# mcu.net
KiCad netlist of a schematic drawn in Altium Designer
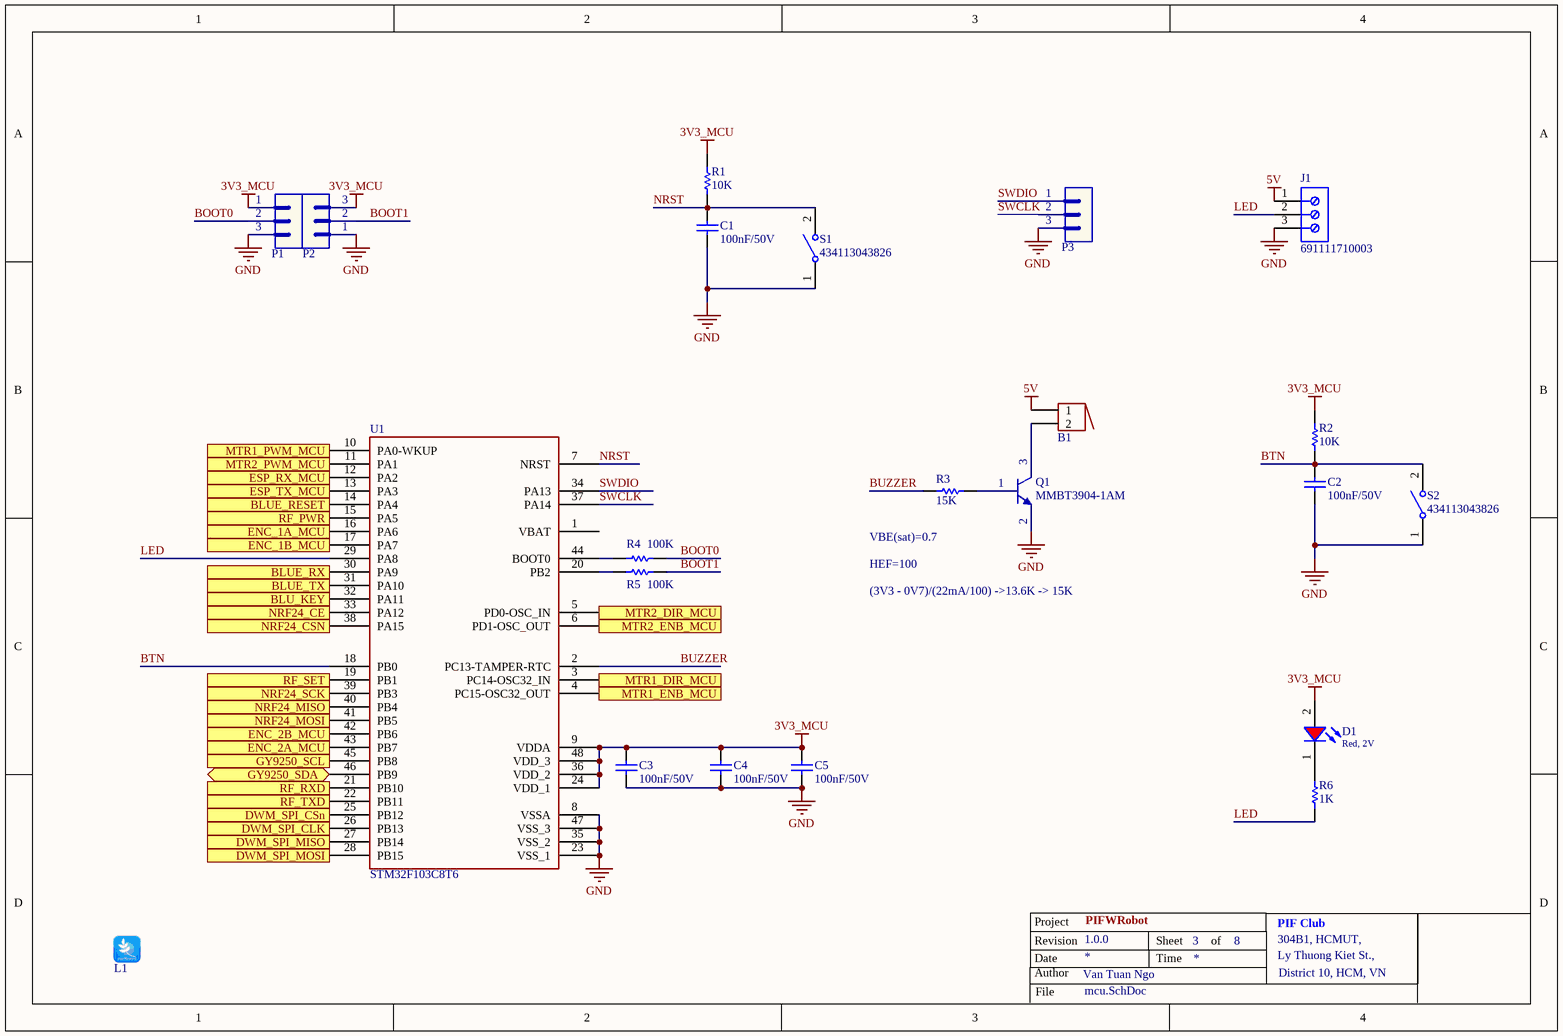
[diagram p0: mcu.SchDoc]

(export (version "E")
  (design (tool "Eeschema 10.0.6"))
  (components
    (comp (ref "B1")
      (value "Buzzer")
      (footprint "BUZZER")
      (fields (field (name "LOCAL SUPPLIER PART NUMBER") "1209 DIP Buzzer 12x9mm"))
      (libsource (lib "PIFWRobot") (part "Buzzer"))
    )
    (comp (ref "C1")
      (value "100nF/50V")
      (footprint "CAP-SM-0805")
      (description "CAP CER 0.1UF 50V Y5V 0805")
      (fields
        (field (name "MANUFACTURER") "Samsung Electro-Mechanics")
        (field (name "MANUFACTURER PART NUMBER") "CL21F104ZBCNNNC")
      )
      (libsource (lib "Capacitor") (part "Cap-100nF-50V-0805"))
    )
    (comp (ref "C2")
      (value "100nF/50V")
      (footprint "CAP-SM-0805")
      (description "CAP CER 0.1UF 50V Y5V 0805")
      (fields
        (field (name "MANUFACTURER") "Samsung Electro-Mechanics")
        (field (name "MANUFACTURER PART NUMBER") "CL21F104ZBCNNNC")
      )
      (libsource (lib "Capacitor") (part "Cap-100nF-50V-0805"))
    )
    (comp (ref "C3")
      (value "100nF/50V")
      (footprint "CAP-SM-0805")
      (description "CAP CER 0.1UF 50V Y5V 0805")
      (fields
        (field (name "MANUFACTURER") "Samsung Electro-Mechanics")
        (field (name "MANUFACTURER PART NUMBER") "CL21F104ZBCNNNC")
      )
      (libsource (lib "Capacitor") (part "Cap-100nF-50V-0805"))
    )
    (comp (ref "C4")
      (value "100nF/50V")
      (footprint "CAP-SM-0805")
      (description "CAP CER 0.1UF 50V Y5V 0805")
      (fields
        (field (name "MANUFACTURER") "Samsung Electro-Mechanics")
        (field (name "MANUFACTURER PART NUMBER") "CL21F104ZBCNNNC")
      )
      (libsource (lib "Capacitor") (part "Cap-100nF-50V-0805"))
    )
    (comp (ref "C5")
      (value "100nF/50V")
      (footprint "CAP-SM-0805")
      (description "CAP CER 0.1UF 50V Y5V 0805")
      (fields
        (field (name "MANUFACTURER") "Samsung Electro-Mechanics")
        (field (name "MANUFACTURER PART NUMBER") "CL21F104ZBCNNNC")
      )
      (libsource (lib "Capacitor") (part "Cap-100nF-50V-0805"))
    )
    (comp (ref "D1")
      (value "Red, 2V")
      (footprint "WL-SMCW_0805")
      (description "WL-SMCW SMT Mono-color Chip LED Waterclear, size 0805, Red, 2V, 140deg")
      (fields
        (field (name "PART NUMBER") "150080RS75000")
        (field (name "LOCAL SUPPLIER PARTNUMBER") "x")
        (field (name "PUBLISHER") "Wurth Elektronik")
      )
      (libsource (lib "LED") (part "0805-Red"))
    )
    (comp (ref "J1")
      (value "691111710003")
      (footprint "691111710003")
      (description "WR-TBL Serie 111 Horizontal Entry Modular, Pressure Clamp, pitch 5mm, 3p")
      (fields (field (name "LOCAL SUPPLIER PART NUMBER") "x") (field (name "PUBLISHER") "Wurth Elektronik"))
      (libsource (lib "Header-Connector") (part "691111710003"))
    )
    (comp (ref "L1")
      (value "LogoPIF")
      (footprint "PIF LOGO BOTTOM OVERLAY")
      (libsource (lib "LogoCLB") (part "LogoPIF"))
    )
    (comp (ref "P1")
      (value "Header 3")
      (footprint "JP3")
      (description "Header, 3-Pin")
      (fields (field (name "LOCAL SUPPLIER PART NUMBER") "x") (field (name "PUBLISHER") "Altium Limited"))
      (libsource (lib "") (part "Header 3_1"))
    )
    (comp (ref "P2")
      (value "Header 3")
      (footprint "JP3")
      (description "Header, 3-Pin")
      (fields (field (name "LOCAL SUPPLIER PART NUMBER") "x") (field (name "PUBLISHER") "Altium Limited"))
      (libsource (lib "Header-Connector") (part "Header 3"))
    )
    (comp (ref "P3")
      (value "Header 3")
      (footprint "JP3")
      (description "Header, 3-Pin")
      (fields (field (name "LOCAL SUPPLIER PART NUMBER") "x") (field (name "PUBLISHER") "Altium Limited"))
      (libsource (lib "") (part "Header 3_1"))
    )
    (comp (ref "Q1")
      (value "MMBT3904-1AM")
      (footprint "SOT23_NEX")
      (libsource (lib "BJT") (part "MMBT2222A"))
    )
    (comp (ref "R1")
      (value "10K")
      (footprint "Resistor:RES-SM-0805")
      (description "RES 10K OHM 1% 1/4W 0805")
      (fields
        (field (name "MANUFACTURER") "Stackpole Electronics Inc")
        (field (name "MANUFACTURER PART NUMBER") "RNCP0805FTD10K0")
      )
      (libsource (lib "Resistor") (part "Res-10k-0805"))
    )
    (comp (ref "R2")
      (value "10K")
      (footprint "Resistor:RES-SM-0805")
      (description "RES 10K OHM 1% 1/4W 0805")
      (fields
        (field (name "MANUFACTURER") "Stackpole Electronics Inc")
        (field (name "MANUFACTURER PART NUMBER") "RNCP0805FTD10K0")
      )
      (libsource (lib "Resistor") (part "Res-10k-0805"))
    )
    (comp (ref "R3")
      (value "15K")
      (footprint "Resistor:RES-SM-0805")
      (description "RES 15K OHM 1% 1/4W 0805")
      (fields
        (field (name "MANUFACTURER") "TE Connectivity Passive Product")
        (field (name "MANUFACTURER PART NUMBER") "CRGCQ0805F15K")
      )
      (libsource (lib "Resistor") (part "Res-15K-0805"))
    )
    (comp (ref "R4")
      (value "100K")
      (footprint "Resistor:RES-SM-0805")
      (description "RES 0 OHM JUMPER 0805")
      (fields
        (field (name "MANUFACTURER") "Vishay Dale")
        (field (name "MANUFACTURER PART NUMBER") "WSL080500000ZEA9")
      )
      (libsource (lib "Resistor") (part "Res-100K-0805"))
    )
    (comp (ref "R5")
      (value "100K")
      (footprint "Resistor:RES-SM-0805")
      (description "RES 0 OHM JUMPER 0805")
      (fields
        (field (name "MANUFACTURER") "Vishay Dale")
        (field (name "MANUFACTURER PART NUMBER") "WSL080500000ZEA9")
      )
      (libsource (lib "Resistor") (part "Res-100K-0805"))
    )
    (comp (ref "R6")
      (value "1K")
      (footprint "Resistor:RES-SM-0805")
      (description "RES 1K OHM 1% 1/4W 0805")
      (fields
        (field (name "MANUFACTURER") "Stackpole Electronics Inc")
        (field (name "MANUFACTURER PART NUMBER") "RNCP0805FTD1K00")
      )
      (libsource (lib "Resistor") (part "Res-1K-0805"))
    )
    (comp (ref "S1")
      (value "434113043826")
      (footprint "434113043826")
      (description "WS-TASV J-Bend SMT Tact Switch 6x3.5mm, height 4.3mm, 260gf")
      (fields (field (name "LOCAL SUPPLIER PART NUMBER") "x") (field (name "PUBLISHER") "Wurth Elektronik"))
      (libsource (lib "switch") (part "434113043826"))
    )
    (comp (ref "S2")
      (value "434113043826")
      (footprint "434113043826")
      (description "WS-TASV J-Bend SMT Tact Switch 6x3.5mm, height 4.3mm, 260gf")
      (fields (field (name "LOCAL SUPPLIER PART NUMBER") "x") (field (name "PUBLISHER") "Wurth Elektronik"))
      (libsource (lib "switch") (part "434113043826"))
    )
    (comp (ref "U1")
      (value "STM32F103C8T6")
      (footprint "LQFP-48")
      (fields (field (name "MANUFACTURER") "ST Electronic"))
      (libsource (lib "PIFWRobot") (part "STM32F103C8T6"))
    )
  )
  (nets
    (net (code "1") (name "/BLUE_RESET") (class "Default")
      (node (ref "U1") (pin "14") (pinfunction "PA4_14") (pintype "passive"))
    )
    (net (code "2") (name "/BLUE_RX") (class "Default")
      (node (ref "U1") (pin "30") (pinfunction "PA9_30") (pintype "passive"))
    )
    (net (code "3") (name "/BLUE_TX") (class "Default")
      (node (ref "U1") (pin "31") (pinfunction "PA10_31") (pintype "passive"))
    )
    (net (code "4") (name "/BLU_KEY") (class "Default")
      (node (ref "U1") (pin "32") (pinfunction "PA11_32") (pintype "passive"))
    )
    (net (code "5") (name "/BOOT0") (class "Default")
      (node (ref "P1") (pin "2") (pinfunction "2_2") (pintype "passive"))
      (node (ref "R4") (pin "2") (pinfunction "2_2") (pintype "passive"))
    )
    (net (code "6") (name "/BOOT1") (class "Default")
      (node (ref "P2") (pin "2") (pinfunction "2_2") (pintype "passive"))
      (node (ref "R5") (pin "1") (pinfunction "1_1") (pintype "passive"))
    )
    (net (code "7") (name "/BTN") (class "Default")
      (node (ref "C2") (pin "2") (pinfunction "2_2") (pintype "passive"))
      (node (ref "R2") (pin "1") (pinfunction "1_1") (pintype "passive"))
      (node (ref "S2") (pin "2") (pinfunction "2_2") (pintype "passive"))
      (node (ref "U1") (pin "18") (pinfunction "PB0_18") (pintype "passive"))
    )
    (net (code "8") (name "/BUZZER") (class "Default")
      (node (ref "R3") (pin "1") (pinfunction "1_1") (pintype "passive"))
      (node (ref "U1") (pin "2") (pinfunction "PC13-TAMPER-RTC_2") (pintype "passive"))
    )
    (net (code "9") (name "/DWM_SPI_CLK") (class "Default")
      (node (ref "U1") (pin "26") (pinfunction "PB13_26") (pintype "passive"))
    )
    (net (code "10") (name "/DWM_SPI_CSn") (class "Default")
      (node (ref "U1") (pin "25") (pinfunction "PB12_25") (pintype "passive"))
    )
    (net (code "11") (name "/DWM_SPI_MISO") (class "Default")
      (node (ref "U1") (pin "27") (pinfunction "PB14_27") (pintype "passive"))
    )
    (net (code "12") (name "/DWM_SPI_MOSI") (class "Default")
      (node (ref "U1") (pin "28") (pinfunction "PB15_28") (pintype "passive"))
    )
    (net (code "13") (name "/ENC_1A_MCU") (class "Default")
      (node (ref "U1") (pin "16") (pinfunction "PA6_16") (pintype "passive"))
    )
    (net (code "14") (name "/ENC_1B_MCU") (class "Default")
      (node (ref "U1") (pin "17") (pinfunction "PA7_17") (pintype "passive"))
    )
    (net (code "15") (name "/ENC_2A_MCU") (class "Default")
      (node (ref "U1") (pin "43") (pinfunction "PB7_43") (pintype "passive"))
    )
    (net (code "16") (name "/ENC_2B_MCU") (class "Default")
      (node (ref "U1") (pin "42") (pinfunction "PB6_42") (pintype "passive"))
    )
    (net (code "17") (name "/ESP_RX_MCU") (class "Default")
      (node (ref "U1") (pin "12") (pinfunction "PA2_12") (pintype "passive"))
    )
    (net (code "18") (name "/ESP_TX_MCU") (class "Default")
      (node (ref "U1") (pin "13") (pinfunction "PA3_13") (pintype "passive"))
    )
    (net (code "19") (name "/GY9250_SCL") (class "Default")
      (node (ref "U1") (pin "45") (pinfunction "PB8_45") (pintype "passive"))
    )
    (net (code "20") (name "/GY9250_SDA") (class "Default")
      (node (ref "U1") (pin "46") (pinfunction "PB9_46") (pintype "passive"))
    )
    (net (code "21") (name "/LED") (class "Default")
      (node (ref "J1") (pin "2") (pinfunction "2_2") (pintype "passive"))
      (node (ref "R6") (pin "1") (pinfunction "1_1") (pintype "passive"))
      (node (ref "U1") (pin "29") (pinfunction "PA8_29") (pintype "passive"))
    )
    (net (code "22") (name "/MTR1_DIR_MCU") (class "Default")
      (node (ref "U1") (pin "3") (pinfunction "PC14-OSC32_IN_3") (pintype "passive"))
    )
    (net (code "23") (name "/MTR1_ENB_MCU") (class "Default")
      (node (ref "U1") (pin "4") (pinfunction "PC15-OSC32_OUT_4") (pintype "passive"))
    )
    (net (code "24") (name "/MTR1_PWM_MCU") (class "Default")
      (node (ref "U1") (pin "10") (pinfunction "PA0-WKUP_10") (pintype "passive"))
    )
    (net (code "25") (name "/MTR2_DIR_MCU") (class "Default")
      (node (ref "U1") (pin "5") (pinfunction "PD0-OSC_IN_5") (pintype "passive"))
    )
    (net (code "26") (name "/MTR2_ENB_MCU") (class "Default")
      (node (ref "U1") (pin "6") (pinfunction "PD1-OSC_OUT_6") (pintype "passive"))
    )
    (net (code "27") (name "/MTR2_PWM_MCU") (class "Default")
      (node (ref "U1") (pin "11") (pinfunction "PA1_11") (pintype "passive"))
    )
    (net (code "28") (name "/NRF24_CE") (class "Default")
      (node (ref "U1") (pin "33") (pinfunction "PA12_33") (pintype "passive"))
    )
    (net (code "29") (name "/NRF24_CSN") (class "Default")
      (node (ref "U1") (pin "38") (pinfunction "PA15_38") (pintype "passive"))
    )
    (net (code "30") (name "/NRF24_MISO") (class "Default")
      (node (ref "U1") (pin "40") (pinfunction "PB4_40") (pintype "passive"))
    )
    (net (code "31") (name "/NRF24_MOSI") (class "Default")
      (node (ref "U1") (pin "41") (pinfunction "PB5_41") (pintype "passive"))
    )
    (net (code "32") (name "/NRF24_SCK") (class "Default")
      (node (ref "U1") (pin "39") (pinfunction "PB3_39") (pintype "passive"))
    )
    (net (code "33") (name "/NRST") (class "Default")
      (node (ref "C1") (pin "2") (pinfunction "2_2") (pintype "passive"))
      (node (ref "R1") (pin "1") (pinfunction "1_1") (pintype "passive"))
      (node (ref "S1") (pin "2") (pinfunction "2_2") (pintype "passive"))
      (node (ref "U1") (pin "7") (pinfunction "NRST_7") (pintype "passive"))
    )
    (net (code "34") (name "/RF_PWR") (class "Default")
      (node (ref "U1") (pin "15") (pinfunction "PA5_15") (pintype "passive"))
    )
    (net (code "35") (name "/RF_RXD") (class "Default")
      (node (ref "U1") (pin "21") (pinfunction "PB10_21") (pintype "passive"))
    )
    (net (code "36") (name "/RF_SET") (class "Default")
      (node (ref "U1") (pin "19") (pinfunction "PB1_19") (pintype "passive"))
    )
    (net (code "37") (name "/RF_TXD") (class "Default")
      (node (ref "U1") (pin "22") (pinfunction "PB11_22") (pintype "passive"))
    )
    (net (code "38") (name "/SWCLK") (class "Default")
      (node (ref "P3") (pin "2") (pinfunction "2_2") (pintype "passive"))
      (node (ref "U1") (pin "37") (pinfunction "PA14_37") (pintype "passive"))
    )
    (net (code "39") (name "/SWDIO") (class "Default")
      (node (ref "P3") (pin "1") (pinfunction "1_1") (pintype "passive"))
      (node (ref "U1") (pin "34") (pinfunction "PA13_34") (pintype "passive"))
    )
    (net (code "40") (name "3V3_MCU") (class "Default")
      (node (ref "C3") (pin "2") (pinfunction "2_2") (pintype "passive"))
      (node (ref "C4") (pin "2") (pinfunction "2_2") (pintype "passive"))
      (node (ref "C5") (pin "2") (pinfunction "2_2") (pintype "passive"))
      (node (ref "D1") (pin "2") (pinfunction "A_2") (pintype "passive"))
      (node (ref "P1") (pin "1") (pinfunction "1_1") (pintype "passive"))
      (node (ref "P2") (pin "3") (pinfunction "3_3") (pintype "passive"))
      (node (ref "R1") (pin "2") (pinfunction "2_2") (pintype "passive"))
      (node (ref "R2") (pin "2") (pinfunction "2_2") (pintype "passive"))
      (node (ref "U1") (pin "24") (pinfunction "VDD_1_24") (pintype "passive"))
      (node (ref "U1") (pin "36") (pinfunction "VDD_2_36") (pintype "passive"))
      (node (ref "U1") (pin "48") (pinfunction "VDD_3_48") (pintype "passive"))
      (node (ref "U1") (pin "9") (pinfunction "VDDA_9") (pintype "passive"))
    )
    (net (code "41") (name "5V") (class "Default")
      (node (ref "B1") (pin "1") (pinfunction "1_1") (pintype "passive"))
      (node (ref "J1") (pin "1") (pinfunction "1_1") (pintype "passive"))
    )
    (net (code "42") (name "GND") (class "Default")
      (node (ref "C1") (pin "1") (pinfunction "1_1") (pintype "passive"))
      (node (ref "C2") (pin "1") (pinfunction "1_1") (pintype "passive"))
      (node (ref "C3") (pin "1") (pinfunction "1_1") (pintype "passive"))
      (node (ref "C4") (pin "1") (pinfunction "1_1") (pintype "passive"))
      (node (ref "C5") (pin "1") (pinfunction "1_1") (pintype "passive"))
      (node (ref "J1") (pin "3") (pinfunction "3_3") (pintype "passive"))
      (node (ref "P1") (pin "3") (pinfunction "3_3") (pintype "passive"))
      (node (ref "P2") (pin "1") (pinfunction "1_1") (pintype "passive"))
      (node (ref "P3") (pin "3") (pinfunction "3_3") (pintype "passive"))
      (node (ref "Q1") (pin "2") (pinfunction "E_2") (pintype "passive"))
      (node (ref "S1") (pin "1") (pinfunction "1_1") (pintype "passive"))
      (node (ref "S2") (pin "1") (pinfunction "1_1") (pintype "passive"))
      (node (ref "U1") (pin "23") (pinfunction "VSS_1_23") (pintype "passive"))
      (node (ref "U1") (pin "35") (pinfunction "VSS_2_35") (pintype "passive"))
      (node (ref "U1") (pin "47") (pinfunction "VSS_3_47") (pintype "passive"))
      (node (ref "U1") (pin "8") (pinfunction "VSSA_8") (pintype "passive"))
    )
    (net (code "43") (name "Net-(D1-K)") (class "Default")
      (node (ref "D1") (pin "1") (pinfunction "K_1") (pintype "passive"))
      (node (ref "R6") (pin "2") (pinfunction "2_2") (pintype "passive"))
    )
    (net (code "44") (name "Net-(Q1-B)") (class "Default")
      (node (ref "Q1") (pin "1") (pinfunction "B_1") (pintype "passive"))
      (node (ref "R3") (pin "2") (pinfunction "2_2") (pintype "passive"))
    )
    (net (code "45") (name "Net-(Q1-C)") (class "Default")
      (node (ref "B1") (pin "2") (pinfunction "2_2") (pintype "passive"))
      (node (ref "Q1") (pin "3") (pinfunction "C_3") (pintype "passive"))
    )
    (net (code "46") (name "Net-(U1-BOOT0)") (class "Default")
      (node (ref "R4") (pin "1") (pinfunction "1_1") (pintype "passive"))
      (node (ref "U1") (pin "44") (pinfunction "BOOT0_44") (pintype "passive"))
    )
    (net (code "47") (name "Net-(U1-PB2)") (class "Default")
      (node (ref "R5") (pin "2") (pinfunction "2_2") (pintype "passive"))
      (node (ref "U1") (pin "20") (pinfunction "PB2_20") (pintype "passive"))
    )
    (net (code "48") (name "unconnected-(U1-VBAT-Pad1)") (class "Default")
      (node (ref "U1") (pin "1") (pinfunction "VBAT_1") (pintype "passive"))
    )
  )
)
